# main_board.net
KiCad netlist of a schematic drawn in EAGLE
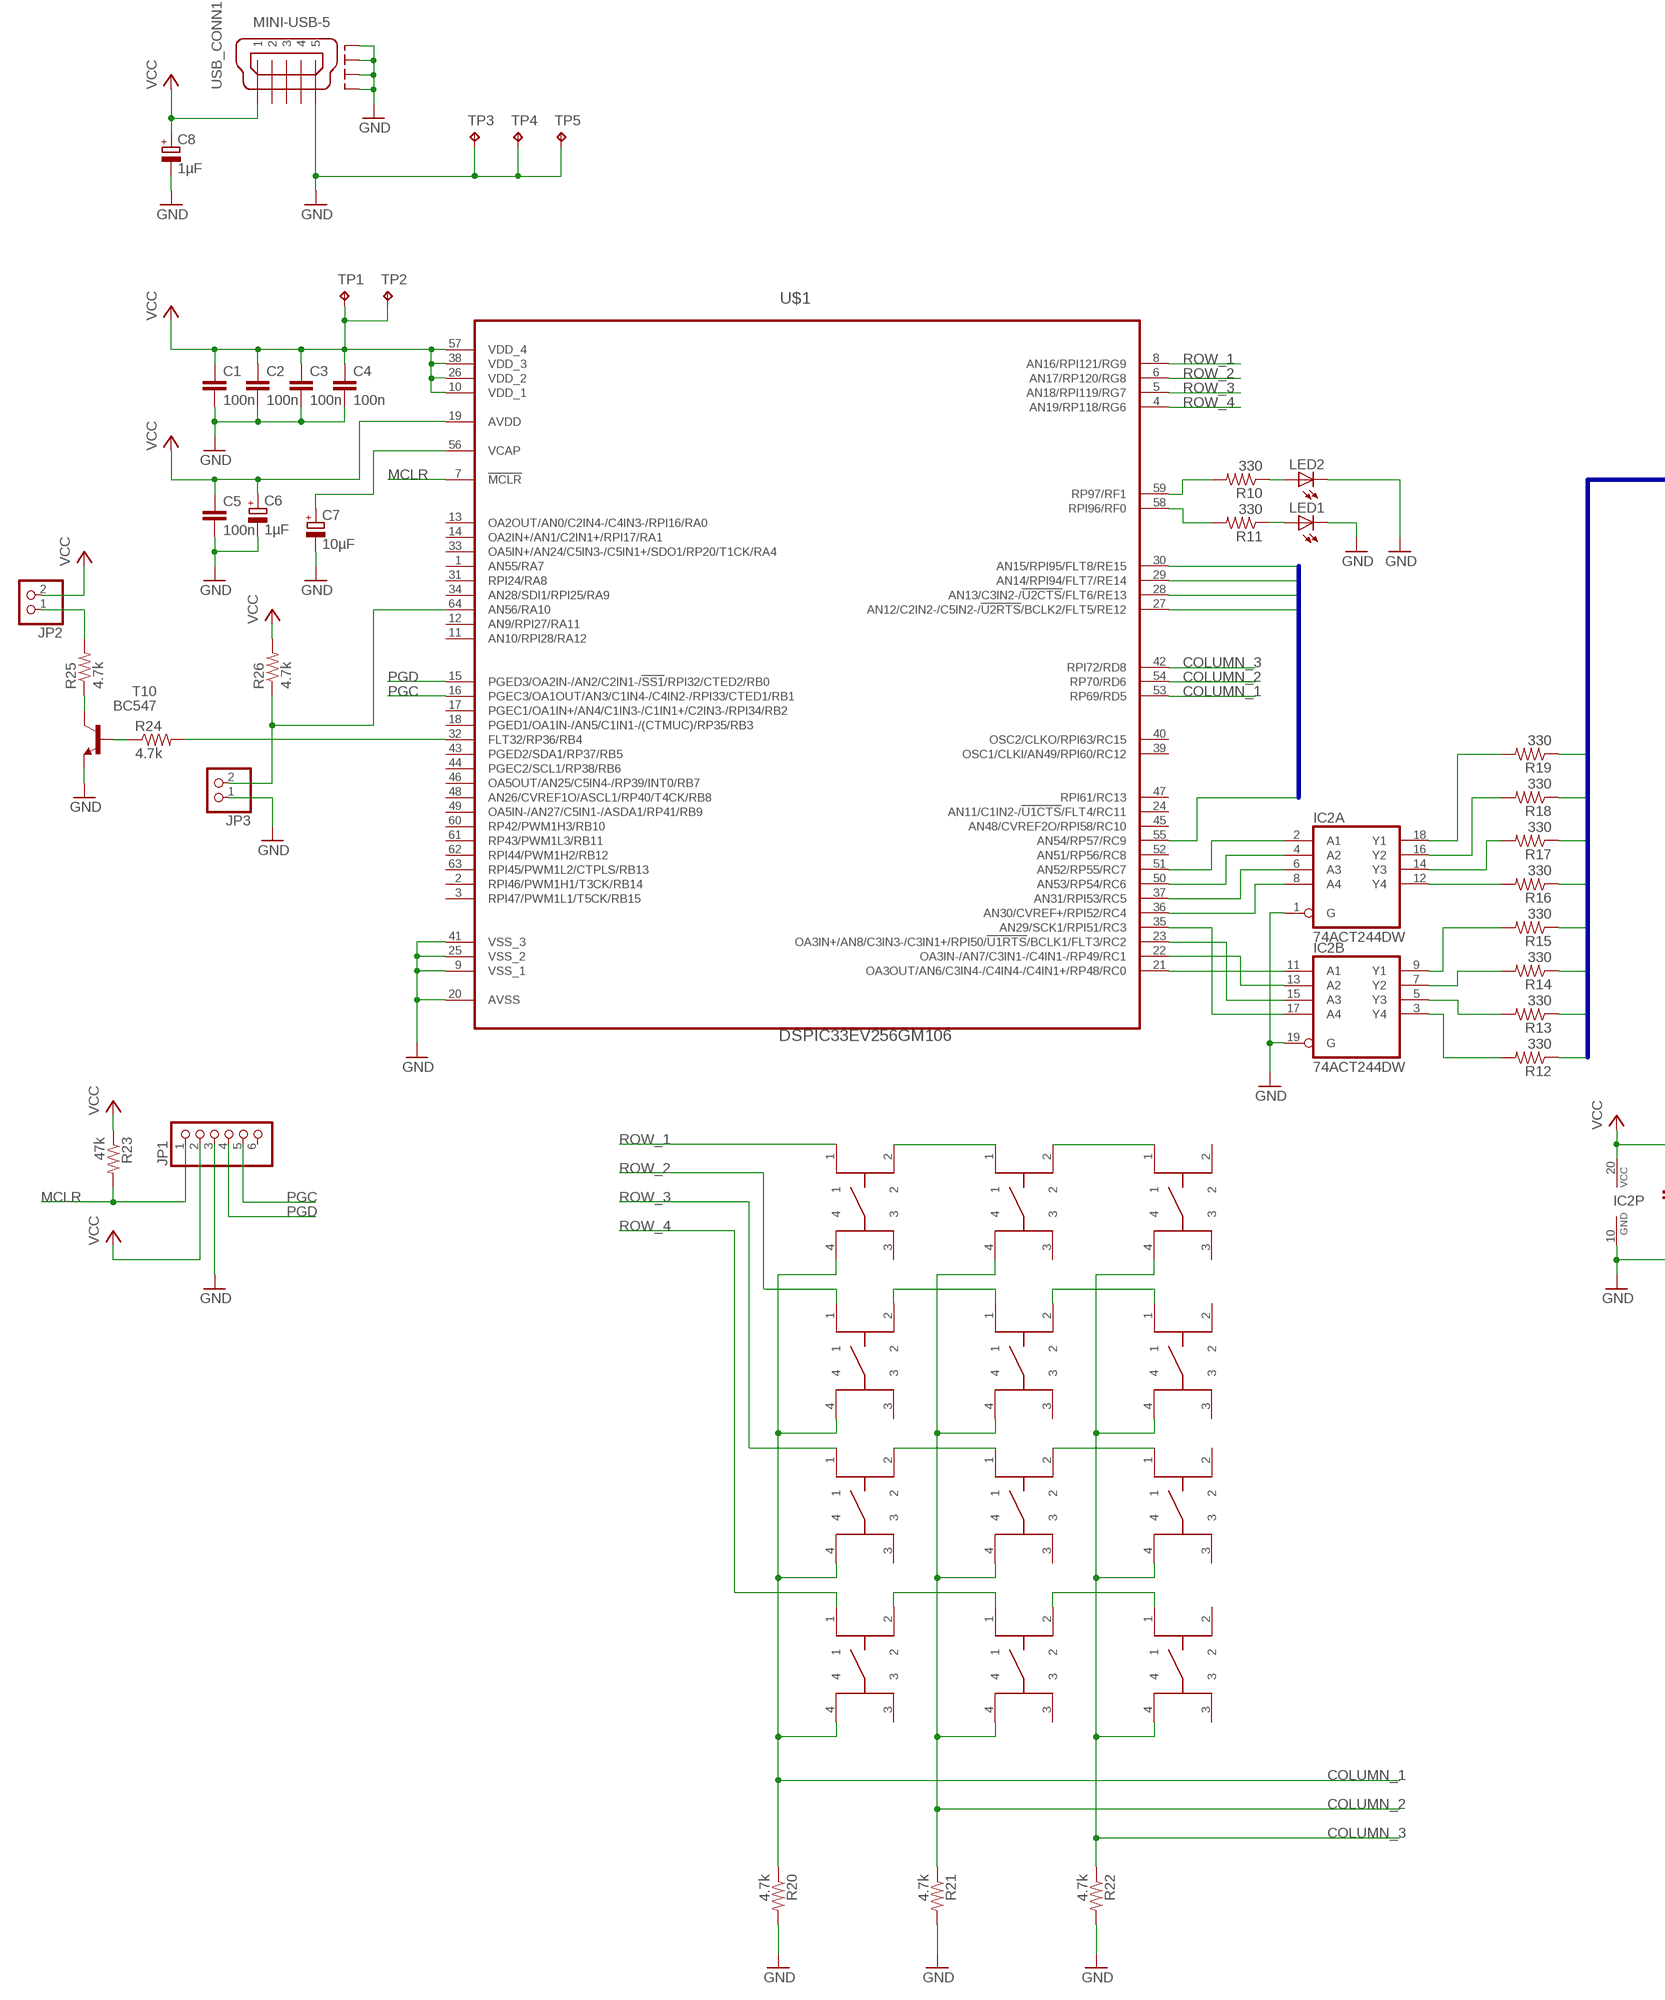
[diagram p0: schematic, sheet 1, part 1 of 2]
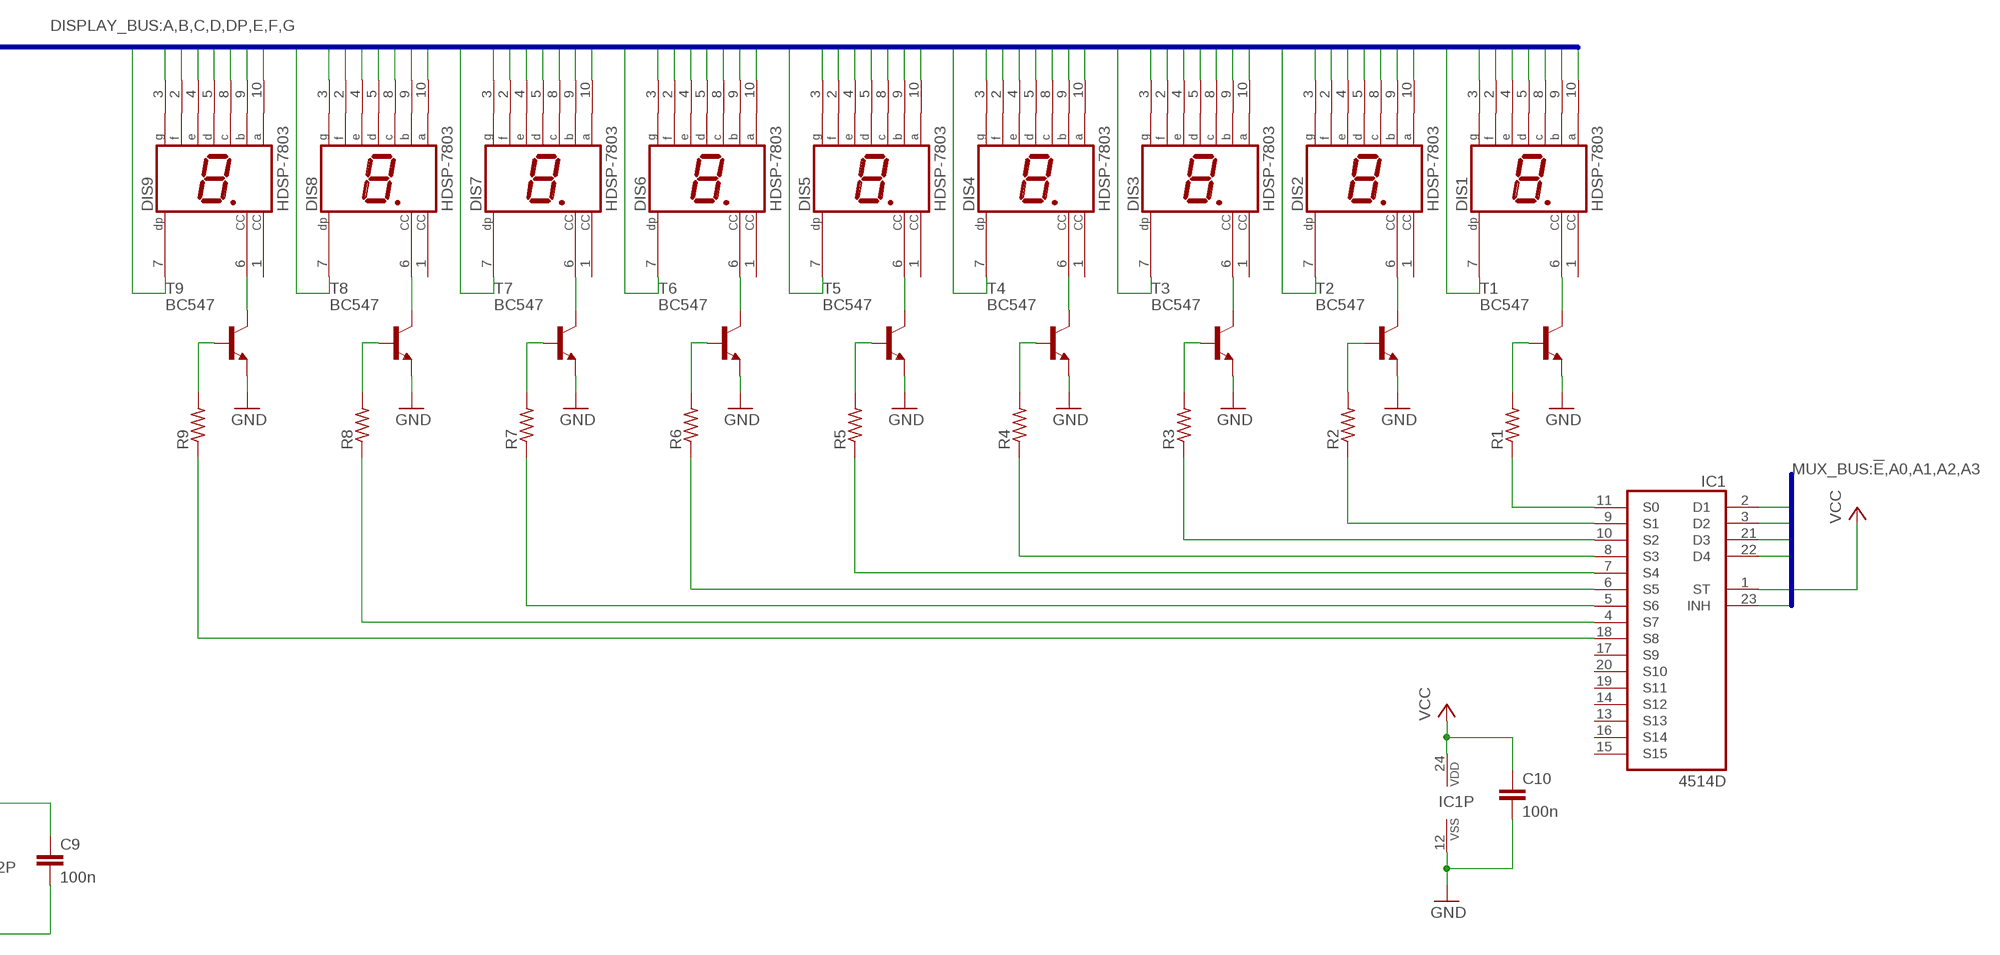
[diagram p1: schematic, sheet 1, part 2 of 2]

(export (version "E")
  (design (tool "Eeschema 10.0.6"))
  (components
    (comp (ref "B1")
      (value "KSC521G")
      (footprint "eagle-import:KSC521G")
      (libsource (lib "eagle-import") (part "KSC521G"))
    )
    (comp (ref "B2")
      (value "KSC521G")
      (footprint "eagle-import:KSC521G")
      (libsource (lib "eagle-import") (part "KSC521G"))
    )
    (comp (ref "B3")
      (value "KSC521G")
      (footprint "eagle-import:KSC521G")
      (libsource (lib "eagle-import") (part "KSC521G"))
    )
    (comp (ref "B4")
      (value "KSC521G")
      (footprint "eagle-import:KSC521G")
      (libsource (lib "eagle-import") (part "KSC521G"))
    )
    (comp (ref "B5")
      (value "KSC521G")
      (footprint "eagle-import:KSC521G")
      (libsource (lib "eagle-import") (part "KSC521G"))
    )
    (comp (ref "B6")
      (value "KSC521G")
      (footprint "eagle-import:KSC521G")
      (libsource (lib "eagle-import") (part "KSC521G"))
    )
    (comp (ref "B7")
      (value "KSC521G")
      (footprint "eagle-import:KSC521G")
      (libsource (lib "eagle-import") (part "KSC521G"))
    )
    (comp (ref "B8")
      (value "KSC521G")
      (footprint "eagle-import:KSC521G")
      (libsource (lib "eagle-import") (part "KSC521G"))
    )
    (comp (ref "B9")
      (value "KSC521G")
      (footprint "eagle-import:KSC521G")
      (libsource (lib "eagle-import") (part "KSC521G"))
    )
    (comp (ref "B10")
      (value "KSC521G")
      (footprint "eagle-import:KSC521G")
      (libsource (lib "eagle-import") (part "KSC521G"))
    )
    (comp (ref "B11")
      (value "KSC521G")
      (footprint "eagle-import:KSC521G")
      (libsource (lib "eagle-import") (part "KSC521G"))
    )
    (comp (ref "B12")
      (value "KSC521G")
      (footprint "eagle-import:KSC521G")
      (libsource (lib "eagle-import") (part "KSC521G"))
    )
    (comp (ref "C1")
      (value "100n")
      (footprint "eagle-import:C050-025X075")
      (libsource (lib "eagle-import") (part "C-EU050-025X075"))
    )
    (comp (ref "C2")
      (value "100n")
      (footprint "eagle-import:C050-025X075")
      (libsource (lib "eagle-import") (part "C-EU050-025X075"))
    )
    (comp (ref "C3")
      (value "100n")
      (footprint "eagle-import:C050-025X075")
      (libsource (lib "eagle-import") (part "C-EU050-025X075"))
    )
    (comp (ref "C4")
      (value "100n")
      (footprint "eagle-import:C050-025X075")
      (libsource (lib "eagle-import") (part "C-EU050-025X075"))
    )
    (comp (ref "C5")
      (value "100n")
      (footprint "eagle-import:C050-025X075")
      (libsource (lib "eagle-import") (part "C-EU050-025X075"))
    )
    (comp (ref "C6")
      (value "1µF")
      (footprint "eagle-import:E2,5-7")
      (libsource (lib "eagle-import") (part "CPOL-EUE2.5-7"))
    )
    (comp (ref "C7")
      (value "10µF")
      (footprint "eagle-import:E2,5-7")
      (libsource (lib "eagle-import") (part "CPOL-EUE2.5-7"))
    )
    (comp (ref "C8")
      (value "1µF")
      (footprint "eagle-import:E2,5-7")
      (libsource (lib "eagle-import") (part "CPOL-EUE2.5-7"))
    )
    (comp (ref "C9")
      (value "100n")
      (footprint "eagle-import:C050-025X075")
      (libsource (lib "eagle-import") (part "C-EU050-025X075"))
    )
    (comp (ref "C10")
      (value "100n")
      (footprint "eagle-import:C050-025X075")
      (libsource (lib "eagle-import") (part "C-EU050-025X075"))
    )
    (comp (ref "DIS1")
      (value "HDSP-7803")
      (footprint "eagle-import:HDSP-A")
      (libsource (lib "eagle-import") (part "HDSP-7803"))
    )
    (comp (ref "DIS2")
      (value "HDSP-7803")
      (footprint "eagle-import:HDSP-A")
      (libsource (lib "eagle-import") (part "HDSP-7803"))
    )
    (comp (ref "DIS3")
      (value "HDSP-7803")
      (footprint "eagle-import:HDSP-A")
      (libsource (lib "eagle-import") (part "HDSP-7803"))
    )
    (comp (ref "DIS4")
      (value "HDSP-7803")
      (footprint "eagle-import:HDSP-A")
      (libsource (lib "eagle-import") (part "HDSP-7803"))
    )
    (comp (ref "DIS5")
      (value "HDSP-7803")
      (footprint "eagle-import:HDSP-A")
      (libsource (lib "eagle-import") (part "HDSP-7803"))
    )
    (comp (ref "DIS6")
      (value "HDSP-7803")
      (footprint "eagle-import:HDSP-A")
      (libsource (lib "eagle-import") (part "HDSP-7803"))
    )
    (comp (ref "DIS7")
      (value "HDSP-7803")
      (footprint "eagle-import:HDSP-A")
      (libsource (lib "eagle-import") (part "HDSP-7803"))
    )
    (comp (ref "DIS8")
      (value "HDSP-7803")
      (footprint "eagle-import:HDSP-A")
      (libsource (lib "eagle-import") (part "HDSP-7803"))
    )
    (comp (ref "DIS9")
      (value "HDSP-7803")
      (footprint "eagle-import:HDSP-A")
      (libsource (lib "eagle-import") (part "HDSP-7803"))
    )
    (comp (ref "IC1")
      (value "4514D")
      (footprint "eagle-import:SO24W")
      (libsource (lib "eagle-import") (part "4514D"))
    )
    (comp (ref "IC2")
      (value "74ACT244DW")
      (footprint "eagle-import:SO20W")
      (libsource (lib "eagle-import") (part "74244DWACT"))
    )
    (comp (ref "JP1")
      (value "PINHD-1X6")
      (footprint "eagle-import:1X06")
      (libsource (lib "eagle-import") (part "PINHD-1X6"))
    )
    (comp (ref "JP2")
      (value "PINHD-1X2")
      (footprint "eagle-import:1X02")
      (libsource (lib "eagle-import") (part "PINHD-1X2"))
    )
    (comp (ref "JP3")
      (value "PINHD-1X2")
      (footprint "eagle-import:1X02")
      (libsource (lib "eagle-import") (part "PINHD-1X2"))
    )
    (comp (ref "LED1")
      (value "LED5MM")
      (footprint "eagle-import:LED5MM")
      (libsource (lib "eagle-import") (part "LED5MM"))
    )
    (comp (ref "LED2")
      (value "LED5MM")
      (footprint "eagle-import:LED5MM")
      (libsource (lib "eagle-import") (part "LED5MM"))
    )
    (comp (ref "R1")
      (value "R-US_0207/10")
      (footprint "eagle-import:0207_10")
      (libsource (lib "eagle-import") (part "R-US_0207/10"))
    )
    (comp (ref "R2")
      (value "R-US_0207/10")
      (footprint "eagle-import:0207_10")
      (libsource (lib "eagle-import") (part "R-US_0207/10"))
    )
    (comp (ref "R3")
      (value "R-US_0207/10")
      (footprint "eagle-import:0207_10")
      (libsource (lib "eagle-import") (part "R-US_0207/10"))
    )
    (comp (ref "R4")
      (value "R-US_0207/10")
      (footprint "eagle-import:0207_10")
      (libsource (lib "eagle-import") (part "R-US_0207/10"))
    )
    (comp (ref "R5")
      (value "R-US_0207/10")
      (footprint "eagle-import:0207_10")
      (libsource (lib "eagle-import") (part "R-US_0207/10"))
    )
    (comp (ref "R6")
      (value "R-US_0207/10")
      (footprint "eagle-import:0207_10")
      (libsource (lib "eagle-import") (part "R-US_0207/10"))
    )
    (comp (ref "R7")
      (value "R-US_0207/10")
      (footprint "eagle-import:0207_10")
      (libsource (lib "eagle-import") (part "R-US_0207/10"))
    )
    (comp (ref "R8")
      (value "R-US_0207/10")
      (footprint "eagle-import:0207_10")
      (libsource (lib "eagle-import") (part "R-US_0207/10"))
    )
    (comp (ref "R9")
      (value "R-US_0207/10")
      (footprint "eagle-import:0207_10")
      (libsource (lib "eagle-import") (part "R-US_0207/10"))
    )
    (comp (ref "R10")
      (value "330")
      (footprint "eagle-import:0207_10")
      (libsource (lib "eagle-import") (part "R-US_0207/10"))
    )
    (comp (ref "R11")
      (value "330")
      (footprint "eagle-import:0207_10")
      (libsource (lib "eagle-import") (part "R-US_0207/10"))
    )
    (comp (ref "R12")
      (value "330")
      (footprint "eagle-import:0207_10")
      (libsource (lib "eagle-import") (part "R-US_0207/10"))
    )
    (comp (ref "R13")
      (value "330")
      (footprint "eagle-import:0207_10")
      (libsource (lib "eagle-import") (part "R-US_0207/10"))
    )
    (comp (ref "R14")
      (value "330")
      (footprint "eagle-import:0207_10")
      (libsource (lib "eagle-import") (part "R-US_0207/10"))
    )
    (comp (ref "R15")
      (value "330")
      (footprint "eagle-import:0207_10")
      (libsource (lib "eagle-import") (part "R-US_0207/10"))
    )
    (comp (ref "R16")
      (value "330")
      (footprint "eagle-import:0207_10")
      (libsource (lib "eagle-import") (part "R-US_0207/10"))
    )
    (comp (ref "R17")
      (value "330")
      (footprint "eagle-import:0207_10")
      (libsource (lib "eagle-import") (part "R-US_0207/10"))
    )
    (comp (ref "R18")
      (value "330")
      (footprint "eagle-import:0207_10")
      (libsource (lib "eagle-import") (part "R-US_0207/10"))
    )
    (comp (ref "R19")
      (value "330")
      (footprint "eagle-import:0207_10")
      (libsource (lib "eagle-import") (part "R-US_0207/10"))
    )
    (comp (ref "R20")
      (value "4.7k")
      (footprint "eagle-import:0207_10")
      (libsource (lib "eagle-import") (part "R-US_0207/10"))
    )
    (comp (ref "R21")
      (value "4.7k")
      (footprint "eagle-import:0207_10")
      (libsource (lib "eagle-import") (part "R-US_0207/10"))
    )
    (comp (ref "R22")
      (value "4.7k")
      (footprint "eagle-import:0207_10")
      (libsource (lib "eagle-import") (part "R-US_0207/10"))
    )
    (comp (ref "R23")
      (value "47k")
      (footprint "eagle-import:0207_10")
      (libsource (lib "eagle-import") (part "R-US_0207/10"))
    )
    (comp (ref "R24")
      (value "4.7k")
      (footprint "eagle-import:0207_10")
      (libsource (lib "eagle-import") (part "R-US_0207/10"))
    )
    (comp (ref "R25")
      (value "4.7k")
      (footprint "eagle-import:0207_10")
      (libsource (lib "eagle-import") (part "R-US_0207/10"))
    )
    (comp (ref "R26")
      (value "4.7k")
      (footprint "eagle-import:0207_10")
      (libsource (lib "eagle-import") (part "R-US_0207/10"))
    )
    (comp (ref "T1")
      (value "BC547")
      (footprint "eagle-import:TO92")
      (libsource (lib "eagle-import") (part "BC547"))
    )
    (comp (ref "T2")
      (value "BC547")
      (footprint "eagle-import:TO92")
      (libsource (lib "eagle-import") (part "BC547"))
    )
    (comp (ref "T3")
      (value "BC547")
      (footprint "eagle-import:TO92")
      (libsource (lib "eagle-import") (part "BC547"))
    )
    (comp (ref "T4")
      (value "BC547")
      (footprint "eagle-import:TO92")
      (libsource (lib "eagle-import") (part "BC547"))
    )
    (comp (ref "T5")
      (value "BC547")
      (footprint "eagle-import:TO92")
      (libsource (lib "eagle-import") (part "BC547"))
    )
    (comp (ref "T6")
      (value "BC547")
      (footprint "eagle-import:TO92")
      (libsource (lib "eagle-import") (part "BC547"))
    )
    (comp (ref "T7")
      (value "BC547")
      (footprint "eagle-import:TO92")
      (libsource (lib "eagle-import") (part "BC547"))
    )
    (comp (ref "T8")
      (value "BC547")
      (footprint "eagle-import:TO92")
      (libsource (lib "eagle-import") (part "BC547"))
    )
    (comp (ref "T9")
      (value "BC547")
      (footprint "eagle-import:TO92")
      (libsource (lib "eagle-import") (part "BC547"))
    )
    (comp (ref "T10")
      (value "BC547")
      (footprint "eagle-import:TO92")
      (libsource (lib "eagle-import") (part "BC547"))
    )
    (comp (ref "TP1")
      (value "TPTP12SQ")
      (footprint "eagle-import:TP12SQ")
      (libsource (lib "eagle-import") (part "TPTP12SQ"))
    )
    (comp (ref "TP2")
      (value "TPTP12SQ")
      (footprint "eagle-import:TP12SQ")
      (libsource (lib "eagle-import") (part "TPTP12SQ"))
    )
    (comp (ref "TP3")
      (value "TPTP12SQ")
      (footprint "eagle-import:TP12SQ")
      (libsource (lib "eagle-import") (part "TPTP12SQ"))
    )
    (comp (ref "TP4")
      (value "TPTP12SQ")
      (footprint "eagle-import:TP12SQ")
      (libsource (lib "eagle-import") (part "TPTP12SQ"))
    )
    (comp (ref "TP5")
      (value "TPTP12SQ")
      (footprint "eagle-import:TP12SQ")
      (libsource (lib "eagle-import") (part "TPTP12SQ"))
    )
    (comp (ref "U$1")
      (value "DSPIC33EV256GM106")
      (footprint "eagle-import:TQFP64-10X10")
      (libsource (lib "eagle-import") (part "DSPIC33EV256GM106"))
    )
    (comp (ref "USB_CONN1")
      (value "MINI-USB-5")
      (footprint "eagle-import:56579-0579")
      (libsource (lib "eagle-import") (part "MINI-USB-5"))
    )
  )
  (nets
    (net (code "5") (name "A") (class "Default")
      (node (ref "DIS1") (pin "10") (pinfunction "A_10") (pintype "passive"))
      (node (ref "DIS2") (pin "10") (pinfunction "A_10") (pintype "passive"))
      (node (ref "DIS3") (pin "10") (pinfunction "A_10") (pintype "passive"))
      (node (ref "DIS4") (pin "10") (pinfunction "A_10") (pintype "passive"))
      (node (ref "DIS5") (pin "10") (pinfunction "A_10") (pintype "passive"))
      (node (ref "DIS6") (pin "10") (pinfunction "A_10") (pintype "passive"))
      (node (ref "DIS7") (pin "10") (pinfunction "A_10") (pintype "passive"))
      (node (ref "DIS8") (pin "10") (pinfunction "A_10") (pintype "passive"))
      (node (ref "DIS9") (pin "10") (pinfunction "A_10") (pintype "passive"))
      (node (ref "R12") (pin "1") (pinfunction "1_1") (pintype "passive"))
    )
    (net (code "6") (name "A0") (class "Default")
      (node (ref "IC1") (pin "2") (pinfunction "D1_2") (pintype "input"))
      (node (ref "U$1") (pin "27") (pinfunction "AN12/C2IN2-/C5IN2-/~{U2RTS}/BCLK2/FLT5/RE12_27") (pintype "bidirectional"))
    )
    (net (code "7") (name "A1") (class "Default")
      (node (ref "IC1") (pin "3") (pinfunction "D2_3") (pintype "input"))
      (node (ref "U$1") (pin "28") (pinfunction "AN13/C3IN2-/~{U2CTS}/FLT6/RE13_28") (pintype "bidirectional"))
    )
    (net (code "8") (name "A2") (class "Default")
      (node (ref "IC1") (pin "21") (pinfunction "D3_21") (pintype "input"))
      (node (ref "U$1") (pin "29") (pinfunction "AN14/RPI94/FLT7/RE14_29") (pintype "bidirectional"))
    )
    (net (code "9") (name "A3") (class "Default")
      (node (ref "IC1") (pin "22") (pinfunction "D4_22") (pintype "input"))
      (node (ref "U$1") (pin "30") (pinfunction "AN15/RPI95/FLT8/RE15_30") (pintype "bidirectional"))
    )
    (net (code "10") (name "B") (class "Default")
      (node (ref "DIS1") (pin "9") (pinfunction "B_9") (pintype "passive"))
      (node (ref "DIS2") (pin "9") (pinfunction "B_9") (pintype "passive"))
      (node (ref "DIS3") (pin "9") (pinfunction "B_9") (pintype "passive"))
      (node (ref "DIS4") (pin "9") (pinfunction "B_9") (pintype "passive"))
      (node (ref "DIS5") (pin "9") (pinfunction "B_9") (pintype "passive"))
      (node (ref "DIS6") (pin "9") (pinfunction "B_9") (pintype "passive"))
      (node (ref "DIS7") (pin "9") (pinfunction "B_9") (pintype "passive"))
      (node (ref "DIS8") (pin "9") (pinfunction "B_9") (pintype "passive"))
      (node (ref "DIS9") (pin "9") (pinfunction "B_9") (pintype "passive"))
      (node (ref "R13") (pin "1") (pinfunction "1_1") (pintype "passive"))
    )
    (net (code "11") (name "C") (class "Default")
      (node (ref "DIS1") (pin "8") (pinfunction "C_8") (pintype "passive"))
      (node (ref "DIS2") (pin "8") (pinfunction "C_8") (pintype "passive"))
      (node (ref "DIS3") (pin "8") (pinfunction "C_8") (pintype "passive"))
      (node (ref "DIS4") (pin "8") (pinfunction "C_8") (pintype "passive"))
      (node (ref "DIS5") (pin "8") (pinfunction "C_8") (pintype "passive"))
      (node (ref "DIS6") (pin "8") (pinfunction "C_8") (pintype "passive"))
      (node (ref "DIS7") (pin "8") (pinfunction "C_8") (pintype "passive"))
      (node (ref "DIS8") (pin "8") (pinfunction "C_8") (pintype "passive"))
      (node (ref "DIS9") (pin "8") (pinfunction "C_8") (pintype "passive"))
      (node (ref "R14") (pin "1") (pinfunction "1_1") (pintype "passive"))
    )
    (net (code "12") (name "COLUMN_1") (class "Default")
      (node (ref "B1") (pin "4") (pinfunction "4_4") (pintype "bidirectional"))
      (node (ref "B11") (pin "4") (pinfunction "4_4") (pintype "bidirectional"))
      (node (ref "B4") (pin "4") (pinfunction "4_4") (pintype "bidirectional"))
      (node (ref "B7") (pin "4") (pinfunction "4_4") (pintype "bidirectional"))
      (node (ref "R20") (pin "1") (pinfunction "1_1") (pintype "passive"))
      (node (ref "U$1") (pin "53") (pinfunction "RP69/RD5_53") (pintype "bidirectional"))
    )
    (net (code "13") (name "COLUMN_2") (class "Default")
      (node (ref "B10") (pin "4") (pinfunction "4_4") (pintype "bidirectional"))
      (node (ref "B2") (pin "4") (pinfunction "4_4") (pintype "bidirectional"))
      (node (ref "B5") (pin "4") (pinfunction "4_4") (pintype "bidirectional"))
      (node (ref "B8") (pin "4") (pinfunction "4_4") (pintype "bidirectional"))
      (node (ref "R21") (pin "1") (pinfunction "1_1") (pintype "passive"))
      (node (ref "U$1") (pin "54") (pinfunction "RP70/RD6_54") (pintype "bidirectional"))
    )
    (net (code "14") (name "COLUMN_3") (class "Default")
      (node (ref "B12") (pin "4") (pinfunction "4_4") (pintype "bidirectional"))
      (node (ref "B3") (pin "4") (pinfunction "4_4") (pintype "bidirectional"))
      (node (ref "B6") (pin "4") (pinfunction "4_4") (pintype "bidirectional"))
      (node (ref "B9") (pin "4") (pinfunction "4_4") (pintype "bidirectional"))
      (node (ref "R22") (pin "1") (pinfunction "1_1") (pintype "passive"))
      (node (ref "U$1") (pin "42") (pinfunction "RPI72/RD8_42") (pintype "bidirectional"))
    )
    (net (code "15") (name "D") (class "Default")
      (node (ref "DIS1") (pin "5") (pinfunction "D_5") (pintype "passive"))
      (node (ref "DIS2") (pin "5") (pinfunction "D_5") (pintype "passive"))
      (node (ref "DIS3") (pin "5") (pinfunction "D_5") (pintype "passive"))
      (node (ref "DIS4") (pin "5") (pinfunction "D_5") (pintype "passive"))
      (node (ref "DIS5") (pin "5") (pinfunction "D_5") (pintype "passive"))
      (node (ref "DIS6") (pin "5") (pinfunction "D_5") (pintype "passive"))
      (node (ref "DIS7") (pin "5") (pinfunction "D_5") (pintype "passive"))
      (node (ref "DIS8") (pin "5") (pinfunction "D_5") (pintype "passive"))
      (node (ref "DIS9") (pin "5") (pinfunction "D_5") (pintype "passive"))
      (node (ref "R15") (pin "1") (pinfunction "1_1") (pintype "passive"))
    )
    (net (code "16") (name "DP") (class "Default")
      (node (ref "DIS1") (pin "7") (pinfunction "DP_7") (pintype "passive"))
      (node (ref "DIS2") (pin "7") (pinfunction "DP_7") (pintype "passive"))
      (node (ref "DIS3") (pin "7") (pinfunction "DP_7") (pintype "passive"))
      (node (ref "DIS4") (pin "7") (pinfunction "DP_7") (pintype "passive"))
      (node (ref "DIS5") (pin "7") (pinfunction "DP_7") (pintype "passive"))
      (node (ref "DIS6") (pin "7") (pinfunction "DP_7") (pintype "passive"))
      (node (ref "DIS7") (pin "7") (pinfunction "DP_7") (pintype "passive"))
      (node (ref "DIS8") (pin "7") (pinfunction "DP_7") (pintype "passive"))
      (node (ref "DIS9") (pin "7") (pinfunction "DP_7") (pintype "passive"))
      (node (ref "R19") (pin "1") (pinfunction "1_1") (pintype "passive"))
    )
    (net (code "17") (name "E") (class "Default")
      (node (ref "DIS1") (pin "4") (pinfunction "E_4") (pintype "passive"))
      (node (ref "DIS2") (pin "4") (pinfunction "E_4") (pintype "passive"))
      (node (ref "DIS3") (pin "4") (pinfunction "E_4") (pintype "passive"))
      (node (ref "DIS4") (pin "4") (pinfunction "E_4") (pintype "passive"))
      (node (ref "DIS5") (pin "4") (pinfunction "E_4") (pintype "passive"))
      (node (ref "DIS6") (pin "4") (pinfunction "E_4") (pintype "passive"))
      (node (ref "DIS7") (pin "4") (pinfunction "E_4") (pintype "passive"))
      (node (ref "DIS8") (pin "4") (pinfunction "E_4") (pintype "passive"))
      (node (ref "DIS9") (pin "4") (pinfunction "E_4") (pintype "passive"))
      (node (ref "R16") (pin "1") (pinfunction "1_1") (pintype "passive"))
    )
    (net (code "18") (name "F") (class "Default")
      (node (ref "DIS1") (pin "2") (pinfunction "F_2") (pintype "passive"))
      (node (ref "DIS2") (pin "2") (pinfunction "F_2") (pintype "passive"))
      (node (ref "DIS3") (pin "2") (pinfunction "F_2") (pintype "passive"))
      (node (ref "DIS4") (pin "2") (pinfunction "F_2") (pintype "passive"))
      (node (ref "DIS5") (pin "2") (pinfunction "F_2") (pintype "passive"))
      (node (ref "DIS6") (pin "2") (pinfunction "F_2") (pintype "passive"))
      (node (ref "DIS7") (pin "2") (pinfunction "F_2") (pintype "passive"))
      (node (ref "DIS8") (pin "2") (pinfunction "F_2") (pintype "passive"))
      (node (ref "DIS9") (pin "2") (pinfunction "F_2") (pintype "passive"))
      (node (ref "R17") (pin "1") (pinfunction "1_1") (pintype "passive"))
    )
    (net (code "19") (name "G") (class "Default")
      (node (ref "DIS1") (pin "3") (pinfunction "G_3") (pintype "passive"))
      (node (ref "DIS2") (pin "3") (pinfunction "G_3") (pintype "passive"))
      (node (ref "DIS3") (pin "3") (pinfunction "G_3") (pintype "passive"))
      (node (ref "DIS4") (pin "3") (pinfunction "G_3") (pintype "passive"))
      (node (ref "DIS5") (pin "3") (pinfunction "G_3") (pintype "passive"))
      (node (ref "DIS6") (pin "3") (pinfunction "G_3") (pintype "passive"))
      (node (ref "DIS7") (pin "3") (pinfunction "G_3") (pintype "passive"))
      (node (ref "DIS8") (pin "3") (pinfunction "G_3") (pintype "passive"))
      (node (ref "DIS9") (pin "3") (pinfunction "G_3") (pintype "passive"))
      (node (ref "R18") (pin "1") (pinfunction "1_1") (pintype "passive"))
    )
    (net (code "20") (name "GND") (class "Default")
      (node (ref "C1") (pin "2") (pinfunction "2_2") (pintype "passive"))
      (node (ref "C10") (pin "2") (pinfunction "2_2") (pintype "passive"))
      (node (ref "C2") (pin "2") (pinfunction "2_2") (pintype "passive"))
      (node (ref "C3") (pin "2") (pinfunction "2_2") (pintype "passive"))
      (node (ref "C4") (pin "2") (pinfunction "2_2") (pintype "passive"))
      (node (ref "C5") (pin "2") (pinfunction "2_2") (pintype "passive"))
      (node (ref "C6") (pin "-") (pinfunction "-_-") (pintype "passive"))
      (node (ref "C7") (pin "-") (pinfunction "-_-") (pintype "passive"))
      (node (ref "C8") (pin "-") (pinfunction "-_-") (pintype "passive"))
      (node (ref "C9") (pin "2") (pinfunction "2_2") (pintype "passive"))
      (node (ref "IC1") (pin "12") (pinfunction "VSS_12") (pintype "power_in"))
      (node (ref "IC2") (pin "1") (pinfunction "G_1") (pintype "input"))
      (node (ref "IC2") (pin "10") (pinfunction "GND_10") (pintype "power_in"))
      (node (ref "IC2") (pin "19") (pinfunction "G_19") (pintype "input"))
      (node (ref "JP1") (pin "3") (pinfunction "3_3") (pintype "passive"))
      (node (ref "JP3") (pin "1") (pinfunction "1_1") (pintype "passive"))
      (node (ref "LED1") (pin "K") (pinfunction "C_K") (pintype "passive"))
      (node (ref "LED2") (pin "K") (pinfunction "C_K") (pintype "passive"))
      (node (ref "R20") (pin "2") (pinfunction "2_2") (pintype "passive"))
      (node (ref "R21") (pin "2") (pinfunction "2_2") (pintype "passive"))
      (node (ref "R22") (pin "2") (pinfunction "2_2") (pintype "passive"))
      (node (ref "T1") (pin "1") (pinfunction "E_1") (pintype "passive"))
      (node (ref "T10") (pin "1") (pinfunction "E_1") (pintype "passive"))
      (node (ref "T2") (pin "1") (pinfunction "E_1") (pintype "passive"))
      (node (ref "T3") (pin "1") (pinfunction "E_1") (pintype "passive"))
      (node (ref "T4") (pin "1") (pinfunction "E_1") (pintype "passive"))
      (node (ref "T5") (pin "1") (pinfunction "E_1") (pintype "passive"))
      (node (ref "T6") (pin "1") (pinfunction "E_1") (pintype "passive"))
      (node (ref "T7") (pin "1") (pinfunction "E_1") (pintype "passive"))
      (node (ref "T8") (pin "1") (pinfunction "E_1") (pintype "passive"))
      (node (ref "T9") (pin "1") (pinfunction "E_1") (pintype "passive"))
      (node (ref "TP3") (pin "TP") (pinfunction "TP_TP") (pintype "input"))
      (node (ref "TP4") (pin "TP") (pinfunction "TP_TP") (pintype "input"))
      (node (ref "TP5") (pin "TP") (pinfunction "TP_TP") (pintype "input"))
      (node (ref "U$1") (pin "20") (pinfunction "AVSS_20") (pintype "power_in"))
      (node (ref "U$1") (pin "25") (pinfunction "VSS_2_25") (pintype "power_in"))
      (node (ref "U$1") (pin "41") (pinfunction "VSS_3_41") (pintype "power_in"))
      (node (ref "U$1") (pin "9") (pinfunction "VSS_1_9") (pintype "power_in"))
      (node (ref "USB_CONN1") (pin "GND") (pinfunction "5_GND") (pintype "passive"))
      (node (ref "USB_CONN1") (pin "SHIELD@1") (pinfunction "S1_SHIELD@1") (pintype "passive"))
      (node (ref "USB_CONN1") (pin "SHIELD@2") (pinfunction "S2_SHIELD@2") (pintype "passive"))
      (node (ref "USB_CONN1") (pin "SHIELD@3") (pinfunction "S3_SHIELD@3") (pintype "passive"))
      (node (ref "USB_CONN1") (pin "SHIELD@4") (pinfunction "S4_SHIELD@4") (pintype "passive"))
    )
    (net (code "21") (name "MCLR") (class "Default")
      (node (ref "JP1") (pin "1") (pinfunction "1_1") (pintype "passive"))
      (node (ref "R23") (pin "2") (pinfunction "2_2") (pintype "passive"))
      (node (ref "U$1") (pin "7") (pinfunction "~{MCLR}_7") (pintype "input"))
    )
    (net (code "22") (name "Net-(B1-Pad2)") (class "Default")
      (node (ref "B1") (pin "2") (pinfunction "2_2") (pintype "bidirectional"))
      (node (ref "B2") (pin "1") (pinfunction "1_1") (pintype "bidirectional"))
    )
    (net (code "23") (name "Net-(B2-Pad2)") (class "Default")
      (node (ref "B2") (pin "2") (pinfunction "2_2") (pintype "bidirectional"))
      (node (ref "B3") (pin "1") (pinfunction "1_1") (pintype "bidirectional"))
    )
    (net (code "24") (name "Net-(B4-Pad2)") (class "Default")
      (node (ref "B4") (pin "2") (pinfunction "2_2") (pintype "bidirectional"))
      (node (ref "B5") (pin "1") (pinfunction "1_1") (pintype "bidirectional"))
    )
    (net (code "25") (name "Net-(B5-Pad2)") (class "Default")
      (node (ref "B5") (pin "2") (pinfunction "2_2") (pintype "bidirectional"))
      (node (ref "B6") (pin "1") (pinfunction "1_1") (pintype "bidirectional"))
    )
    (net (code "26") (name "Net-(B7-Pad2)") (class "Default")
      (node (ref "B7") (pin "2") (pinfunction "2_2") (pintype "bidirectional"))
      (node (ref "B8") (pin "1") (pinfunction "1_1") (pintype "bidirectional"))
    )
    (net (code "27") (name "Net-(B8-Pad2)") (class "Default")
      (node (ref "B8") (pin "2") (pinfunction "2_2") (pintype "bidirectional"))
      (node (ref "B9") (pin "1") (pinfunction "1_1") (pintype "bidirectional"))
    )
    (net (code "28") (name "Net-(B10-Pad1)") (class "Default")
      (node (ref "B10") (pin "1") (pinfunction "1_1") (pintype "bidirectional"))
      (node (ref "B11") (pin "2") (pinfunction "2_2") (pintype "bidirectional"))
    )
    (net (code "29") (name "Net-(B10-Pad2)") (class "Default")
      (node (ref "B10") (pin "2") (pinfunction "2_2") (pintype "bidirectional"))
      (node (ref "B12") (pin "1") (pinfunction "1_1") (pintype "bidirectional"))
    )
    (net (code "30") (name "Net-(IC1A-S0)") (class "Default")
      (node (ref "IC1") (pin "11") (pinfunction "S0_11") (pintype "output"))
      (node (ref "R1") (pin "1") (pinfunction "1_1") (pintype "passive"))
    )
    (net (code "31") (name "Net-(IC1A-S1)") (class "Default")
      (node (ref "IC1") (pin "9") (pinfunction "S1_9") (pintype "output"))
      (node (ref "R2") (pin "1") (pinfunction "1_1") (pintype "passive"))
    )
    (net (code "32") (name "Net-(IC1A-S2)") (class "Default")
      (node (ref "IC1") (pin "10") (pinfunction "S2_10") (pintype "output"))
      (node (ref "R3") (pin "1") (pinfunction "1_1") (pintype "passive"))
    )
    (net (code "33") (name "Net-(IC1A-S3)") (class "Default")
      (node (ref "IC1") (pin "8") (pinfunction "S3_8") (pintype "output"))
      (node (ref "R4") (pin "1") (pinfunction "1_1") (pintype "passive"))
    )
    (net (code "34") (name "Net-(IC1A-S4)") (class "Default")
      (node (ref "IC1") (pin "7") (pinfunction "S4_7") (pintype "output"))
      (node (ref "R5") (pin "1") (pinfunction "1_1") (pintype "passive"))
    )
    (net (code "35") (name "Net-(IC1A-S5)") (class "Default")
      (node (ref "IC1") (pin "6") (pinfunction "S5_6") (pintype "output"))
      (node (ref "R6") (pin "1") (pinfunction "1_1") (pintype "passive"))
    )
    (net (code "36") (name "Net-(IC1A-S6)") (class "Default")
      (node (ref "IC1") (pin "5") (pinfunction "S6_5") (pintype "output"))
      (node (ref "R7") (pin "1") (pinfunction "1_1") (pintype "passive"))
    )
    (net (code "37") (name "Net-(IC1A-S7)") (class "Default")
      (node (ref "IC1") (pin "4") (pinfunction "S7_4") (pintype "output"))
      (node (ref "R8") (pin "1") (pinfunction "1_1") (pintype "passive"))
    )
    (net (code "38") (name "Net-(IC1A-S8)") (class "Default")
      (node (ref "IC1") (pin "18") (pinfunction "S8_18") (pintype "output"))
      (node (ref "R9") (pin "1") (pinfunction "1_1") (pintype "passive"))
    )
    (net (code "39") (name "Net-(IC2A-A1)") (class "Default")
      (node (ref "IC2") (pin "2") (pinfunction "A1_2") (pintype "input"))
      (node (ref "U$1") (pin "51") (pinfunction "AN52/RP55/RC7_51") (pintype "bidirectional"))
    )
    (net (code "40") (name "Net-(IC2A-A2)") (class "Default")
      (node (ref "IC2") (pin "4") (pinfunction "A2_4") (pintype "input"))
      (node (ref "U$1") (pin "50") (pinfunction "AN53/RP54/RC6_50") (pintype "bidirectional"))
    )
    (net (code "41") (name "Net-(IC2A-A3)") (class "Default")
      (node (ref "IC2") (pin "6") (pinfunction "A3_6") (pintype "input"))
      (node (ref "U$1") (pin "37") (pinfunction "AN31/RPI53/RC5_37") (pintype "bidirectional"))
    )
    (net (code "42") (name "Net-(IC2A-A4)") (class "Default")
      (node (ref "IC2") (pin "8") (pinfunction "A4_8") (pintype "input"))
      (node (ref "U$1") (pin "36") (pinfunction "AN30/CVREF+/RPI52/RC4_36") (pintype "bidirectional"))
    )
    (net (code "43") (name "Net-(IC2A-Y1)") (class "Default")
      (node (ref "IC2") (pin "18") (pinfunction "Y1_18") (pintype "tri_state"))
      (node (ref "R19") (pin "2") (pinfunction "2_2") (pintype "passive"))
    )
    (net (code "44") (name "Net-(IC2A-Y2)") (class "Default")
      (node (ref "IC2") (pin "16") (pinfunction "Y2_16") (pintype "tri_state"))
      (node (ref "R18") (pin "2") (pinfunction "2_2") (pintype "passive"))
    )
    (net (code "45") (name "Net-(IC2A-Y3)") (class "Default")
      (node (ref "IC2") (pin "14") (pinfunction "Y3_14") (pintype "tri_state"))
      (node (ref "R17") (pin "2") (pinfunction "2_2") (pintype "passive"))
    )
    (net (code "46") (name "Net-(IC2A-Y4)") (class "Default")
      (node (ref "IC2") (pin "12") (pinfunction "Y4_12") (pintype "tri_state"))
      (node (ref "R16") (pin "2") (pinfunction "2_2") (pintype "passive"))
    )
    (net (code "47") (name "Net-(IC2B-A1)") (class "Default")
      (node (ref "IC2") (pin "11") (pinfunction "A1_11") (pintype "input"))
      (node (ref "U$1") (pin "21") (pinfunction "OA3OUT/AN6/C3IN4-/C4IN4-/C4IN1+/RP48/RC0_21") (pintype "bidirectional"))
    )
    (net (code "48") (name "Net-(IC2B-A2)") (class "Default")
      (node (ref "IC2") (pin "13") (pinfunction "A2_13") (pintype "input"))
      (node (ref "U$1") (pin "22") (pinfunction "OA3IN-/AN7/C3IN1-/C4IN1-/RP49/RC1_22") (pintype "bidirectional"))
    )
    (net (code "49") (name "Net-(IC2B-A3)") (class "Default")
      (node (ref "IC2") (pin "15") (pinfunction "A3_15") (pintype "input"))
      (node (ref "U$1") (pin "23") (pinfunction "OA3IN+/AN8/C3IN3-/C3IN1+/RPI50/~{U1RTS}/BCLK1/FLT3/RC2_23") (pintype "bidirectional"))
    )
    (net (code "50") (name "Net-(IC2B-A4)") (class "Default")
      (node (ref "IC2") (pin "17") (pinfunction "A4_17") (pintype "input"))
      (node (ref "U$1") (pin "35") (pinfunction "AN29/SCK1/RPI51/RC3_35") (pintype "bidirectional"))
    )
    (net (code "51") (name "Net-(IC2B-Y1)") (class "Default")
      (node (ref "IC2") (pin "9") (pinfunction "Y1_9") (pintype "tri_state"))
      (node (ref "R15") (pin "2") (pinfunction "2_2") (pintype "passive"))
    )
    (net (code "52") (name "Net-(IC2B-Y2)") (class "Default")
      (node (ref "IC2") (pin "7") (pinfunction "Y2_7") (pintype "tri_state"))
      (node (ref "R14") (pin "2") (pinfunction "2_2") (pintype "passive"))
    )
    (net (code "53") (name "Net-(IC2B-Y3)") (class "Default")
      (node (ref "IC2") (pin "5") (pinfunction "Y3_5") (pintype "tri_state"))
      (node (ref "R13") (pin "2") (pinfunction "2_2") (pintype "passive"))
    )
    (net (code "54") (name "Net-(IC2B-Y4)") (class "Default")
      (node (ref "IC2") (pin "3") (pinfunction "Y4_3") (pintype "tri_state"))
      (node (ref "R12") (pin "2") (pinfunction "2_2") (pintype "passive"))
    )
    (net (code "55") (name "Net-(JP2-Pad1)") (class "Default")
      (node (ref "JP2") (pin "1") (pinfunction "1_1") (pintype "passive"))
      (node (ref "R25") (pin "2") (pinfunction "2_2") (pintype "passive"))
    )
    (net (code "56") (name "Net-(LED1-PadA)") (class "Default")
      (node (ref "LED1") (pin "A") (pinfunction "A_A") (pintype "passive"))
      (node (ref "R11") (pin "1") (pinfunction "1_1") (pintype "passive"))
    )
    (net (code "57") (name "Net-(LED2-PadA)") (class "Default")
      (node (ref "LED2") (pin "A") (pinfunction "A_A") (pintype "passive"))
      (node (ref "R10") (pin "1") (pinfunction "1_1") (pintype "passive"))
    )
    (net (code "58") (name "Net-(T1-B)") (class "Default")
      (node (ref "R1") (pin "2") (pinfunction "2_2") (pintype "passive"))
      (node (ref "T1") (pin "2") (pinfunction "B_2") (pintype "passive"))
    )
    (net (code "59") (name "Net-(T1-C)") (class "Default")
      (node (ref "DIS1") (pin "6") (pinfunction "CC_6") (pintype "passive"))
      (node (ref "T1") (pin "3") (pinfunction "C_3") (pintype "passive"))
    )
    (net (code "60") (name "Net-(T2-B)") (class "Default")
      (node (ref "R2") (pin "2") (pinfunction "2_2") (pintype "passive"))
      (node (ref "T2") (pin "2") (pinfunction "B_2") (pintype "passive"))
    )
    (net (code "61") (name "Net-(T2-C)") (class "Default")
      (node (ref "DIS2") (pin "6") (pinfunction "CC_6") (pintype "passive"))
      (node (ref "T2") (pin "3") (pinfunction "C_3") (pintype "passive"))
    )
    (net (code "62") (name "Net-(T3-B)") (class "Default")
      (node (ref "R3") (pin "2") (pinfunction "2_2") (pintype "passive"))
      (node (ref "T3") (pin "2") (pinfunction "B_2") (pintype "passive"))
    )
    (net (code "63") (name "Net-(T3-C)") (class "Default")
      (node (ref "DIS3") (pin "6") (pinfunction "CC_6") (pintype "passive"))
      (node (ref "T3") (pin "3") (pinfunction "C_3") (pintype "passive"))
    )
    (net (code "64") (name "Net-(T4-B)") (class "Default")
      (node (ref "R4") (pin "2") (pinfunction "2_2") (pintype "passive"))
      (node (ref "T4") (pin "2") (pinfunction "B_2") (pintype "passive"))
    )
    (net (code "65") (name "Net-(T4-C)") (class "Default")
      (node (ref "DIS4") (pin "6") (pinfunction "CC_6") (pintype "passive"))
      (node (ref "T4") (pin "3") (pinfunction "C_3") (pintype "passive"))
    )
    (net (code "66") (name "Net-(T5-B)") (class "Default")
      (node (ref "R5") (pin "2") (pinfunction "2_2") (pintype "passive"))
      (node (ref "T5") (pin "2") (pinfunction "B_2") (pintype "passive"))
    )
    (net (code "67") (name "Net-(T5-C)") (class "Default")
      (node (ref "DIS5") (pin "6") (pinfunction "CC_6") (pintype "passive"))
      (node (ref "T5") (pin "3") (pinfunction "C_3") (pintype "passive"))
    )
    (net (code "68") (name "Net-(T6-B)") (class "Default")
      (node (ref "R6") (pin "2") (pinfunction "2_2") (pintype "passive"))
      (node (ref "T6") (pin "2") (pinfunction "B_2") (pintype "passive"))
    )
    (net (code "69") (name "Net-(T6-C)") (class "Default")
      (node (ref "DIS6") (pin "6") (pinfunction "CC_6") (pintype "passive"))
      (node (ref "T6") (pin "3") (pinfunction "C_3") (pintype "passive"))
    )
    (net (code "70") (name "Net-(T7-B)") (class "Default")
      (node (ref "R7") (pin "2") (pinfunction "2_2") (pintype "passive"))
      (node (ref "T7") (pin "2") (pinfunction "B_2") (pintype "passive"))
    )
    (net (code "71") (name "Net-(T7-C)") (class "Default")
      (node (ref "DIS7") (pin "6") (pinfunction "CC_6") (pintype "passive"))
      (node (ref "T7") (pin "3") (pinfunction "C_3") (pintype "passive"))
    )
    (net (code "72") (name "Net-(T8-B)") (class "Default")
      (node (ref "R8") (pin "2") (pinfunction "2_2") (pintype "passive"))
      (node (ref "T8") (pin "2") (pinfunction "B_2") (pintype "passive"))
    )
    (net (code "73") (name "Net-(T8-C)") (class "Default")
      (node (ref "DIS8") (pin "6") (pinfunction "CC_6") (pintype "passive"))
      (node (ref "T8") (pin "3") (pinfunction "C_3") (pintype "passive"))
    )
    (net (code "74") (name "Net-(T9-B)") (class "Default")
      (node (ref "R9") (pin "2") (pinfunction "2_2") (pintype "passive"))
      (node (ref "T9") (pin "2") (pinfunction "B_2") (pintype "passive"))
    )
    (net (code "75") (name "Net-(T9-C)") (class "Default")
      (node (ref "DIS9") (pin "6") (pinfunction "CC_6") (pintype "passive"))
      (node (ref "T9") (pin "3") (pinfunction "C_3") (pintype "passive"))
    )
    (net (code "76") (name "Net-(T10-B)") (class "Default")
      (node (ref "R24") (pin "1") (pinfunction "1_1") (pintype "passive"))
      (node (ref "T10") (pin "2") (pinfunction "B_2") (pintype "passive"))
    )
    (net (code "77") (name "Net-(T10-C)") (class "Default")
      (node (ref "R25") (pin "1") (pinfunction "1_1") (pintype "passive"))
      (node (ref "T10") (pin "3") (pinfunction "C_3") (pintype "passive"))
    )
    (net (code "78") (name "Net-(U$1-AN56{slash}RA10)") (class "Default")
      (node (ref "JP3") (pin "2") (pinfunction "2_2") (pintype "passive"))
      (node (ref "R26") (pin "1") (pinfunction "1_1") (pintype "passive"))
      (node (ref "U$1") (pin "64") (pinfunction "AN56/RA10_64") (pintype "bidirectional"))
    )
    (net (code "79") (name "Net-(U$1-FLT32{slash}RP36{slash}RB4)") (class "Default")
      (node (ref "R24") (pin "2") (pinfunction "2_2") (pintype "passive"))
      (node (ref "U$1") (pin "32") (pinfunction "FLT32/RP36/RB4_32") (pintype "bidirectional"))
    )
    (net (code "80") (name "Net-(U$1-RP97{slash}RF1)") (class "Default")
      (node (ref "R10") (pin "2") (pinfunction "2_2") (pintype "passive"))
      (node (ref "U$1") (pin "59") (pinfunction "RP97/RF1_59") (pintype "bidirectional"))
    )
    (net (code "81") (name "Net-(U$1-RPI96{slash}RF0)") (class "Default")
      (node (ref "R11") (pin "2") (pinfunction "2_2") (pintype "passive"))
      (node (ref "U$1") (pin "58") (pinfunction "RPI96/RF0_58") (pintype "bidirectional"))
    )
    (net (code "82") (name "Net-(U$1-VCAP)") (class "Default")
      (node (ref "C7") (pin "+") (pinfunction "+_+") (pintype "passive"))
      (node (ref "U$1") (pin "56") (pinfunction "VCAP_56") (pintype "power_in"))
    )
    (net (code "83") (name "PGC") (class "Default")
      (node (ref "JP1") (pin "5") (pinfunction "5_5") (pintype "passive"))
      (node (ref "U$1") (pin "16") (pinfunction "PGEC3/OA1OUT/AN3/C1IN4-/C4IN2-/RPI33/CTED1/RB1_16") (pintype "bidirectional"))
    )
    (net (code "84") (name "PGD") (class "Default")
      (node (ref "JP1") (pin "4") (pinfunction "4_4") (pintype "passive"))
      (node (ref "U$1") (pin "15") (pinfunction "PGED3/OA2IN-/AN2/C2IN1-/~{SS1}/RPI32/CTED2/RB0_15") (pintype "bidirectional"))
    )
    (net (code "85") (name "ROW_1") (class "Default")
      (node (ref "B1") (pin "1") (pinfunction "1_1") (pintype "bidirectional"))
      (node (ref "U$1") (pin "8") (pinfunction "AN16/RPI121/RG9_8") (pintype "bidirectional"))
    )
    (net (code "86") (name "ROW_2") (class "Default")
      (node (ref "B4") (pin "1") (pinfunction "1_1") (pintype "bidirectional"))
      (node (ref "U$1") (pin "6") (pinfunction "AN17/RP120/RG8_6") (pintype "bidirectional"))
    )
    (net (code "87") (name "ROW_3") (class "Default")
      (node (ref "B7") (pin "1") (pinfunction "1_1") (pintype "bidirectional"))
      (node (ref "U$1") (pin "5") (pinfunction "AN18/RPI119/RG7_5") (pintype "bidirectional"))
    )
    (net (code "88") (name "ROW_4") (class "Default")
      (node (ref "B11") (pin "1") (pinfunction "1_1") (pintype "bidirectional"))
      (node (ref "U$1") (pin "4") (pinfunction "AN19/RP118/RG6_4") (pintype "bidirectional"))
    )
    (net (code "89") (name "VCC") (class "Default")
      (node (ref "C1") (pin "1") (pinfunction "1_1") (pintype "passive"))
      (node (ref "C10") (pin "1") (pinfunction "1_1") (pintype "passive"))
      (node (ref "C2") (pin "1") (pinfunction "1_1") (pintype "passive"))
      (node (ref "C3") (pin "1") (pinfunction "1_1") (pintype "passive"))
      (node (ref "C4") (pin "1") (pinfunction "1_1") (pintype "passive"))
      (node (ref "C5") (pin "1") (pinfunction "1_1") (pintype "passive"))
      (node (ref "C6") (pin "+") (pinfunction "+_+") (pintype "passive"))
      (node (ref "C8") (pin "+") (pinfunction "+_+") (pintype "passive"))
      (node (ref "C9") (pin "1") (pinfunction "1_1") (pintype "passive"))
      (node (ref "IC1") (pin "1") (pinfunction "ST_1") (pintype "input"))
      (node (ref "IC1") (pin "24") (pinfunction "VDD_24") (pintype "power_in"))
      (node (ref "IC2") (pin "20") (pinfunction "VCC_20") (pintype "power_in"))
      (node (ref "JP1") (pin "2") (pinfunction "2_2") (pintype "passive"))
      (node (ref "JP2") (pin "2") (pinfunction "2_2") (pintype "passive"))
      (node (ref "R23") (pin "1") (pinfunction "1_1") (pintype "passive"))
      (node (ref "R26") (pin "2") (pinfunction "2_2") (pintype "passive"))
      (node (ref "TP1") (pin "TP") (pinfunction "TP_TP") (pintype "input"))
      (node (ref "TP2") (pin "TP") (pinfunction "TP_TP") (pintype "input"))
      (node (ref "U$1") (pin "10") (pinfunction "VDD_1_10") (pintype "power_in"))
      (node (ref "U$1") (pin "19") (pinfunction "AVDD_19") (pintype "power_in"))
      (node (ref "U$1") (pin "26") (pinfunction "VDD_2_26") (pintype "power_in"))
      (node (ref "U$1") (pin "38") (pinfunction "VDD_3_38") (pintype "power_in"))
      (node (ref "U$1") (pin "57") (pinfunction "VDD_4_57") (pintype "power_in"))
      (node (ref "USB_CONN1") (pin "VBUS") (pinfunction "1_VBUS") (pintype "passive"))
    )
    (net (code "90") (name "unconnected-(B1-Pad3)") (class "Default")
      (node (ref "B1") (pin "3") (pinfunction "3_3") (pintype "bidirectional"))
    )
    (net (code "91") (name "unconnected-(B2-Pad3)") (class "Default")
      (node (ref "B2") (pin "3") (pinfunction "3_3") (pintype "bidirectional"))
    )
    (net (code "92") (name "unconnected-(B3-Pad2)") (class "Default")
      (node (ref "B3") (pin "2") (pinfunction "2_2") (pintype "bidirectional"))
    )
    (net (code "93") (name "unconnected-(B3-Pad3)") (class "Default")
      (node (ref "B3") (pin "3") (pinfunction "3_3") (pintype "bidirectional"))
    )
    (net (code "94") (name "unconnected-(B4-Pad3)") (class "Default")
      (node (ref "B4") (pin "3") (pinfunction "3_3") (pintype "bidirectional"))
    )
    (net (code "95") (name "unconnected-(B5-Pad3)") (class "Default")
      (node (ref "B5") (pin "3") (pinfunction "3_3") (pintype "bidirectional"))
    )
    (net (code "96") (name "unconnected-(B6-Pad2)") (class "Default")
      (node (ref "B6") (pin "2") (pinfunction "2_2") (pintype "bidirectional"))
    )
    (net (code "97") (name "unconnected-(B6-Pad3)") (class "Default")
      (node (ref "B6") (pin "3") (pinfunction "3_3") (pintype "bidirectional"))
    )
    (net (code "98") (name "unconnected-(B7-Pad3)") (class "Default")
      (node (ref "B7") (pin "3") (pinfunction "3_3") (pintype "bidirectional"))
    )
    (net (code "99") (name "unconnected-(B8-Pad3)") (class "Default")
      (node (ref "B8") (pin "3") (pinfunction "3_3") (pintype "bidirectional"))
    )
    (net (code "100") (name "unconnected-(B9-Pad2)") (class "Default")
      (node (ref "B9") (pin "2") (pinfunction "2_2") (pintype "bidirectional"))
    )
    (net (code "101") (name "unconnected-(B9-Pad3)") (class "Default")
      (node (ref "B9") (pin "3") (pinfunction "3_3") (pintype "bidirectional"))
    )
    (net (code "102") (name "unconnected-(B10-Pad3)") (class "Default")
      (node (ref "B10") (pin "3") (pinfunction "3_3") (pintype "bidirectional"))
    )
    (net (code "103") (name "unconnected-(B11-Pad3)") (class "Default")
      (node (ref "B11") (pin "3") (pinfunction "3_3") (pintype "bidirectional"))
    )
    (net (code "104") (name "unconnected-(B12-Pad2)") (class "Default")
      (node (ref "B12") (pin "2") (pinfunction "2_2") (pintype "bidirectional"))
    )
    (net (code "105") (name "unconnected-(B12-Pad3)") (class "Default")
      (node (ref "B12") (pin "3") (pinfunction "3_3") (pintype "bidirectional"))
    )
    (net (code "106") (name "unconnected-(DIS1-CC-Pad1)") (class "Default")
      (node (ref "DIS1") (pin "1") (pinfunction "CC_1") (pintype "passive"))
    )
    (net (code "107") (name "unconnected-(DIS2-CC-Pad1)") (class "Default")
      (node (ref "DIS2") (pin "1") (pinfunction "CC_1") (pintype "passive"))
    )
    (net (code "108") (name "unconnected-(DIS3-CC-Pad1)") (class "Default")
      (node (ref "DIS3") (pin "1") (pinfunction "CC_1") (pintype "passive"))
    )
    (net (code "109") (name "unconnected-(DIS4-CC-Pad1)") (class "Default")
      (node (ref "DIS4") (pin "1") (pinfunction "CC_1") (pintype "passive"))
    )
    (net (code "110") (name "unconnected-(DIS5-CC-Pad1)") (class "Default")
      (node (ref "DIS5") (pin "1") (pinfunction "CC_1") (pintype "passive"))
    )
    (net (code "111") (name "unconnected-(DIS6-CC-Pad1)") (class "Default")
      (node (ref "DIS6") (pin "1") (pinfunction "CC_1") (pintype "passive"))
    )
    (net (code "112") (name "unconnected-(DIS7-CC-Pad1)") (class "Default")
      (node (ref "DIS7") (pin "1") (pinfunction "CC_1") (pintype "passive"))
    )
    (net (code "113") (name "unconnected-(DIS8-CC-Pad1)") (class "Default")
      (node (ref "DIS8") (pin "1") (pinfunction "CC_1") (pintype "passive"))
    )
    (net (code "114") (name "unconnected-(DIS9-CC-Pad1)") (class "Default")
      (node (ref "DIS9") (pin "1") (pinfunction "CC_1") (pintype "passive"))
    )
    (net (code "115") (name "unconnected-(IC1A-S9-Pad17)") (class "Default")
      (node (ref "IC1") (pin "17") (pinfunction "S9_17") (pintype "output"))
    )
    (net (code "116") (name "unconnected-(IC1A-S10-Pad20)") (class "Default")
      (node (ref "IC1") (pin "20") (pinfunction "S10_20") (pintype "output"))
    )
    (net (code "117") (name "unconnected-(IC1A-S11-Pad19)") (class "Default")
      (node (ref "IC1") (pin "19") (pinfunction "S11_19") (pintype "output"))
    )
    (net (code "118") (name "unconnected-(IC1A-S12-Pad14)") (class "Default")
      (node (ref "IC1") (pin "14") (pinfunction "S12_14") (pintype "output"))
    )
    (net (code "119") (name "unconnected-(IC1A-S13-Pad13)") (class "Default")
      (node (ref "IC1") (pin "13") (pinfunction "S13_13") (pintype "output"))
    )
    (net (code "120") (name "unconnected-(IC1A-S14-Pad16)") (class "Default")
      (node (ref "IC1") (pin "16") (pinfunction "S14_16") (pintype "output"))
    )
    (net (code "121") (name "unconnected-(IC1A-S15-Pad15)") (class "Default")
      (node (ref "IC1") (pin "15") (pinfunction "S15_15") (pintype "output"))
    )
    (net (code "122") (name "unconnected-(JP1-Pad6)") (class "Default")
      (node (ref "JP1") (pin "6") (pinfunction "6_6") (pintype "passive"))
    )
    (net (code "123") (name "unconnected-(U$1-AN9{slash}RPI27{slash}RA11-Pad12)") (class "Default")
      (node (ref "U$1") (pin "12") (pinfunction "AN9/RPI27/RA11_12") (pintype "bidirectional"))
    )
    (net (code "124") (name "unconnected-(U$1-AN10{slash}RPI28{slash}RA12-Pad11)") (class "Default")
      (node (ref "U$1") (pin "11") (pinfunction "AN10/RPI28/RA12_11") (pintype "bidirectional"))
    )
    (net (code "125") (name "unconnected-(U$1-AN11{slash}C1IN2-{slash}~{U1CTS}{slash}FLT4{slash}RC11-Pad24)") (class "Default")
      (node (ref "U$1") (pin "24") (pinfunction "AN11/C1IN2-/~{U1CTS}/FLT4/RC11_24") (pintype "bidirectional"))
    )
    (net (code "126") (name "unconnected-(U$1-AN26{slash}CVREF1O{slash}ASCL1{slash}RP40{slash}T4CK{slash}RB8-Pad48)") (class "Default")
      (node (ref "U$1") (pin "48") (pinfunction "AN26/CVREF1O/ASCL1/RP40/T4CK/RB8_48") (pintype "bidirectional"))
    )
    (net (code "127") (name "unconnected-(U$1-AN28{slash}SDI1{slash}RPI25{slash}RA9-Pad34)") (class "Default")
      (node (ref "U$1") (pin "34") (pinfunction "AN28/SDI1/RPI25/RA9_34") (pintype "bidirectional"))
    )
    (net (code "128") (name "unconnected-(U$1-AN48{slash}CVREF2O{slash}RPI58{slash}RC10-Pad45)") (class "Default")
      (node (ref "U$1") (pin "45") (pinfunction "AN48/CVREF2O/RPI58/RC10_45") (pintype "bidirectional"))
    )
    (net (code "129") (name "unconnected-(U$1-AN51{slash}RP56{slash}RC8-Pad52)") (class "Default")
      (node (ref "U$1") (pin "52") (pinfunction "AN51/RP56/RC8_52") (pintype "bidirectional"))
    )
    (net (code "130") (name "unconnected-(U$1-AN55{slash}RA7-Pad1)") (class "Default")
      (node (ref "U$1") (pin "1") (pinfunction "AN55/RA7_1") (pintype "bidirectional"))
    )
    (net (code "131") (name "unconnected-(U$1-OA2IN+{slash}AN1{slash}C2IN1+{slash}RPI17{slash}RA1-Pad14)") (class "Default")
      (node (ref "U$1") (pin "14") (pinfunction "OA2IN+/AN1/C2IN1+/RPI17/RA1_14") (pintype "bidirectional"))
    )
    (net (code "132") (name "unconnected-(U$1-OA2OUT{slash}AN0{slash}C2IN4-{slash}C4IN3-{slash}RPI16{slash}RA0-Pad13)") (class "Default")
      (node (ref "U$1") (pin "13") (pinfunction "OA2OUT/AN0/C2IN4-/C4IN3-/RPI16/RA0_13") (pintype "bidirectional"))
    )
    (net (code "133") (name "unconnected-(U$1-OA5IN+{slash}AN24{slash}C5IN3-{slash}C5IN1+{slash}SDO1{slash}RP20{slash}T1CK{slash}RA4-Pad33)") (class "Default")
      (node (ref "U$1") (pin "33") (pinfunction "OA5IN+/AN24/C5IN3-/C5IN1+/SDO1/RP20/T1CK/RA4_33") (pintype "bidirectional"))
    )
    (net (code "134") (name "unconnected-(U$1-OA5IN-{slash}AN27{slash}C5IN1-{slash}ASDA1{slash}RP41{slash}RB9-Pad49)") (class "Default")
      (node (ref "U$1") (pin "49") (pinfunction "OA5IN-/AN27/C5IN1-/ASDA1/RP41/RB9_49") (pintype "bidirectional"))
    )
    (net (code "135") (name "unconnected-(U$1-OA5OUT{slash}AN25{slash}C5IN4-{slash}RP39{slash}INT0{slash}RB7-Pad46)") (class "Default")
      (node (ref "U$1") (pin "46") (pinfunction "OA5OUT/AN25/C5IN4-/RP39/INT0/RB7_46") (pintype "bidirectional"))
    )
    (net (code "136") (name "unconnected-(U$1-OSC1{slash}CLKI{slash}AN49{slash}RPI60{slash}RC12-Pad39)") (class "Default")
      (node (ref "U$1") (pin "39") (pinfunction "OSC1/CLKI/AN49/RPI60/RC12_39") (pintype "bidirectional"))
    )
    (net (code "137") (name "unconnected-(U$1-OSC2{slash}CLKO{slash}RPI63{slash}RC15-Pad40)") (class "Default")
      (node (ref "U$1") (pin "40") (pinfunction "OSC2/CLKO/RPI63/RC15_40") (pintype "bidirectional"))
    )
    (net (code "138") (name "unconnected-(U$1-PGEC1{slash}OA1IN+{slash}AN4{slash}C1IN3-{slash}C1IN1+{slash}C2IN3-{slash}RPI34{slash}RB2-Pad17)") (class "Default")
      (node (ref "U$1") (pin "17") (pinfunction "PGEC1/OA1IN+/AN4/C1IN3-/C1IN1+/C2IN3-/RPI34/RB2_17") (pintype "bidirectional"))
    )
    (net (code "139") (name "unconnected-(U$1-PGEC2{slash}SCL1{slash}RP38{slash}RB6-Pad44)") (class "Default")
      (node (ref "U$1") (pin "44") (pinfunction "PGEC2/SCL1/RP38/RB6_44") (pintype "bidirectional"))
    )
    (net (code "140") (name "unconnected-(U$1-PGED1{slash}OA1IN-{slash}AN5{slash}C1IN1-{slash}(CTMUC){slash}RP35{slash}RB3-Pad18)") (class "Default")
      (node (ref "U$1") (pin "18") (pinfunction "PGED1/OA1IN-/AN5/C1IN1-/(CTMUC)/RP35/RB3_18") (pintype "bidirectional"))
    )
    (net (code "141") (name "unconnected-(U$1-PGED2{slash}SDA1{slash}RP37{slash}RB5-Pad43)") (class "Default")
      (node (ref "U$1") (pin "43") (pinfunction "PGED2/SDA1/RP37/RB5_43") (pintype "bidirectional"))
    )
    (net (code "142") (name "unconnected-(U$1-RP42{slash}PWM1H3{slash}RB10-Pad60)") (class "Default")
      (node (ref "U$1") (pin "60") (pinfunction "RP42/PWM1H3/RB10_60") (pintype "bidirectional"))
    )
    (net (code "143") (name "unconnected-(U$1-RP43{slash}PWM1L3{slash}RB11-Pad61)") (class "Default")
      (node (ref "U$1") (pin "61") (pinfunction "RP43/PWM1L3/RB11_61") (pintype "bidirectional"))
    )
    (net (code "144") (name "unconnected-(U$1-RPI24{slash}RA8-Pad31)") (class "Default")
      (node (ref "U$1") (pin "31") (pinfunction "RPI24/RA8_31") (pintype "bidirectional"))
    )
    (net (code "145") (name "unconnected-(U$1-RPI44{slash}PWM1H2{slash}RB12-Pad62)") (class "Default")
      (node (ref "U$1") (pin "62") (pinfunction "RPI44/PWM1H2/RB12_62") (pintype "bidirectional"))
    )
    (net (code "146") (name "unconnected-(U$1-RPI45{slash}PWM1L2{slash}CTPLS{slash}RB13-Pad63)") (class "Default")
      (node (ref "U$1") (pin "63") (pinfunction "RPI45/PWM1L2/CTPLS/RB13_63") (pintype "bidirectional"))
    )
    (net (code "147") (name "unconnected-(U$1-RPI46{slash}PWM1H1{slash}T3CK{slash}RB14-Pad2)") (class "Default")
      (node (ref "U$1") (pin "2") (pinfunction "RPI46/PWM1H1/T3CK/RB14_2") (pintype "bidirectional"))
    )
    (net (code "148") (name "unconnected-(U$1-RPI47{slash}PWM1L1{slash}T5CK{slash}RB15-Pad3)") (class "Default")
      (node (ref "U$1") (pin "3") (pinfunction "RPI47/PWM1L1/T5CK/RB15_3") (pintype "bidirectional"))
    )
    (net (code "149") (name "unconnected-(U$1-RPI61{slash}RC13-Pad47)") (class "Default")
      (node (ref "U$1") (pin "47") (pinfunction "RPI61/RC13_47") (pintype "bidirectional"))
    )
    (net (code "150") (name "unconnected-(USB_CONN1-2-PadDN)") (class "Default")
      (node (ref "USB_CONN1") (pin "DN") (pinfunction "2_DN") (pintype "passive"))
    )
    (net (code "151") (name "unconnected-(USB_CONN1-3-PadDP)") (class "Default")
      (node (ref "USB_CONN1") (pin "DP") (pinfunction "3_DP") (pintype "passive"))
    )
    (net (code "152") (name "unconnected-(USB_CONN1-4-PadNC)") (class "Default")
      (node (ref "USB_CONN1") (pin "NC") (pinfunction "4_NC") (pintype "passive"))
    )
    (net (code "153") (name "~{E}") (class "Default")
      (node (ref "IC1") (pin "23") (pinfunction "INH_23") (pintype "input"))
      (node (ref "U$1") (pin "55") (pinfunction "AN54/RP57/RC9_55") (pintype "bidirectional"))
    )
  )
)
